# 5v-power.net
KiCad netlist of a schematic drawn in EAGLE
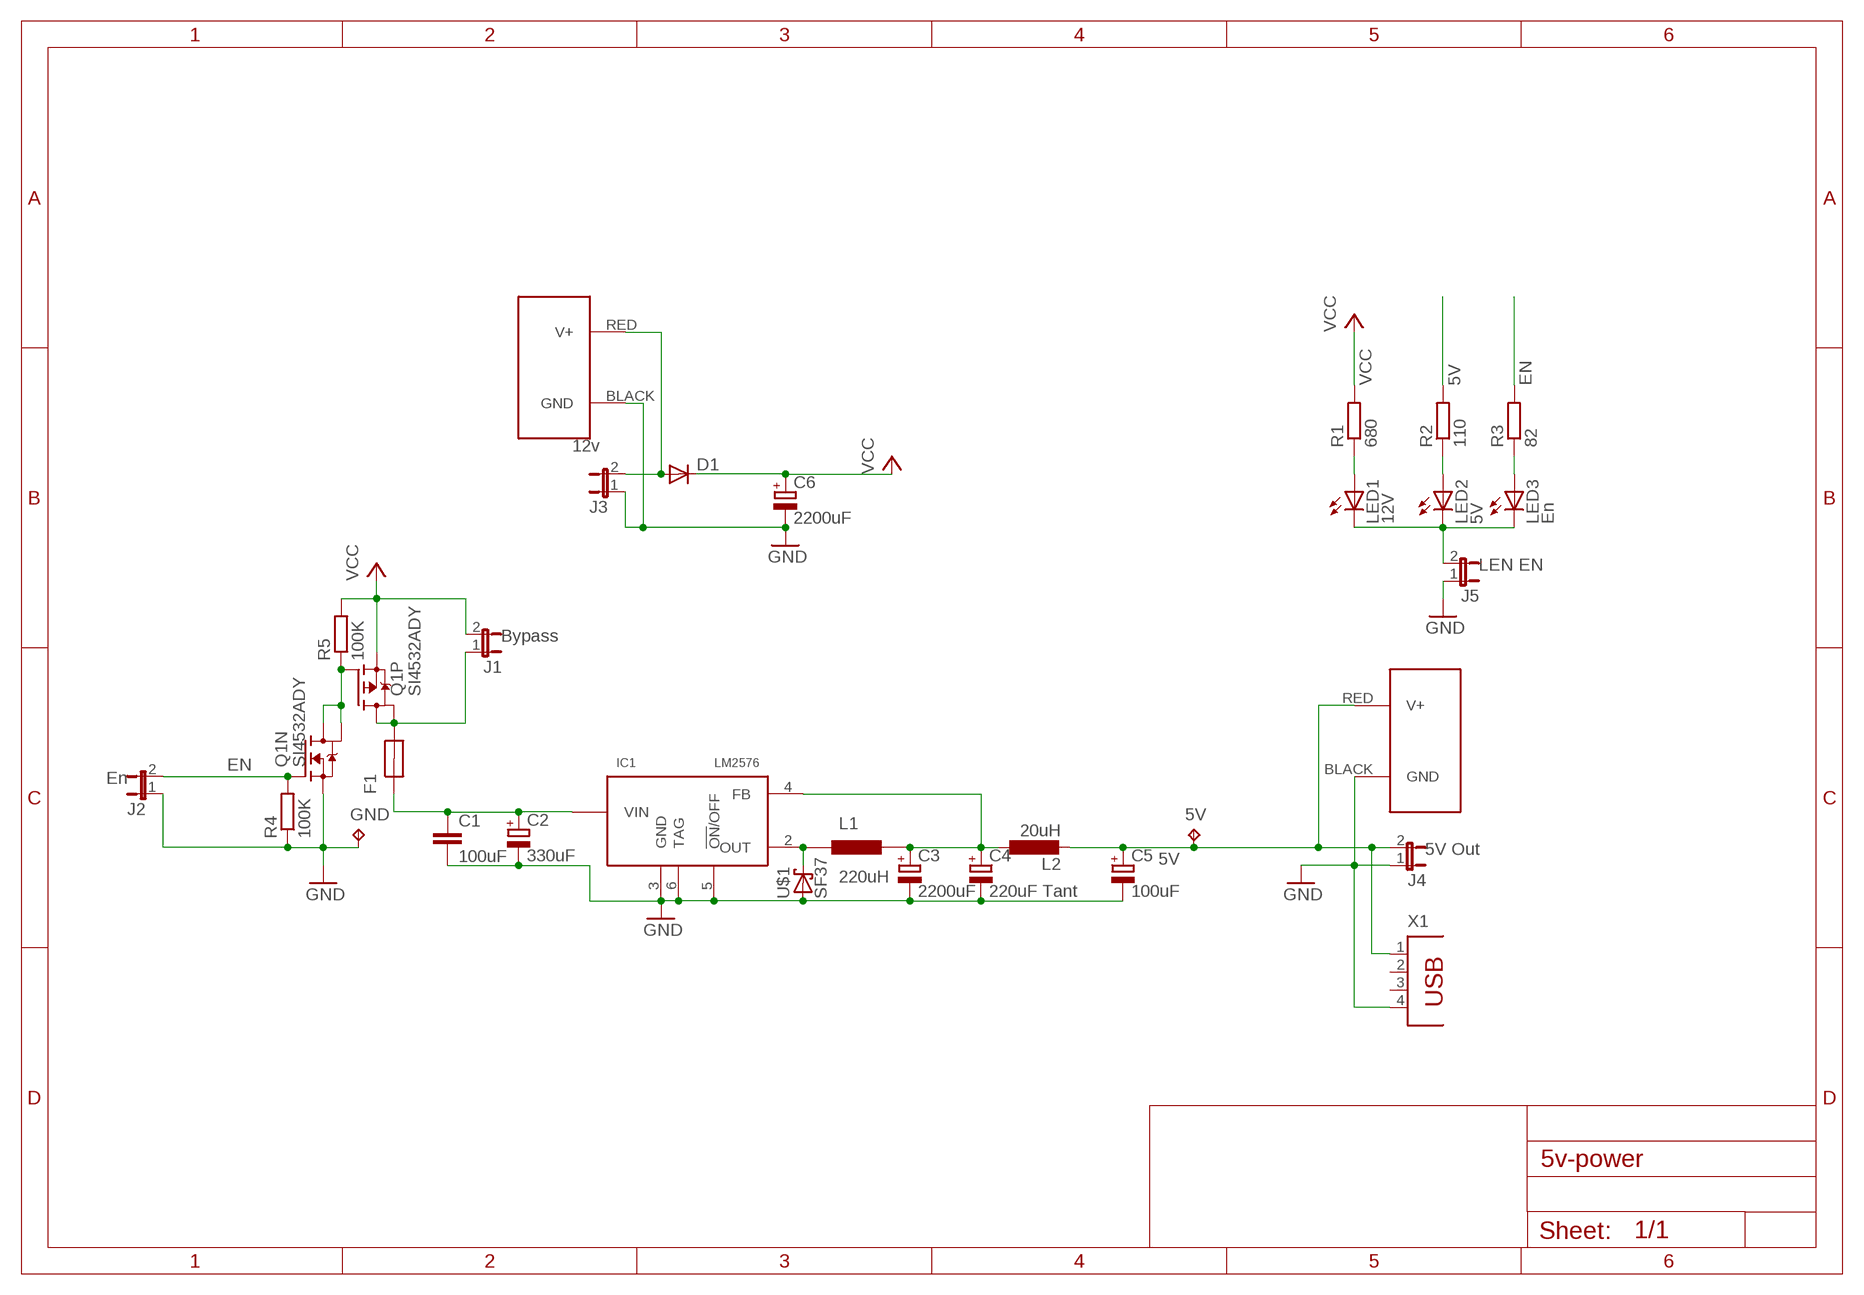
[diagram p0: schematic, sheet 1]

(export (version "E")
  (design (tool "Eeschema 10.0.6"))
  (components
    (comp (ref "5V")
      (value "5V B")
      (footprint "eagle-import:B1,27")
      (libsource (lib "eagle-import") (part "TPB1,27"))
    )
    (comp (ref "C1")
      (value "100uF")
      (footprint "eagle-import:C1210K")
      (libsource (lib "eagle-import") (part "C-EUC1210K"))
    )
    (comp (ref "C2")
      (value "330uF")
      (footprint "eagle-import:E5-8,5")
      (libsource (lib "eagle-import") (part "CPOL-EUE5-8.5"))
    )
    (comp (ref "C3")
      (value "2200uF")
      (footprint "eagle-import:E5-13")
      (libsource (lib "eagle-import") (part "CPOL-EUE5-13"))
    )
    (comp (ref "C4")
      (value "220uF Tant")
      (footprint "eagle-import:B_3528-21R")
      (libsource (lib "eagle-import") (part "CPOL-EUB/3528-21R"))
    )
    (comp (ref "C5")
      (value "100uF")
      (footprint "eagle-import:PANASONIC_E")
      (libsource (lib "eagle-import") (part "CPOL-EUE"))
    )
    (comp (ref "C6")
      (value "2200uF")
      (footprint "eagle-import:E5-13")
      (libsource (lib "eagle-import") (part "CPOL-EUE5-13"))
    )
    (comp (ref "D1")
      (value "DIODE-SMB")
      (footprint "eagle-import:SMB")
      (libsource (lib "eagle-import") (part "DIODE-SMB"))
    )
    (comp (ref "F1")
      (value "MF-MSMF110")
      (footprint "eagle-import:1812")
      (libsource (lib "eagle-import") (part "MF-MSMF110"))
    )
    (comp (ref "GND")
      (value "5V B")
      (footprint "eagle-import:B1,27")
      (libsource (lib "eagle-import") (part "TPB1,27"))
    )
    (comp (ref "IC1")
      (value "LM2576")
      (footprint "eagle-import:TO263")
      (libsource (lib "eagle-import") (part "LM2576"))
    )
    (comp (ref "J1")
      (value "Bypass")
      (footprint "eagle-import:2-MOLEX")
      (libsource (lib "eagle-import") (part "2-PIN-MOLEX"))
    )
    (comp (ref "J2")
      (value "En")
      (footprint "eagle-import:2-MOLEX")
      (libsource (lib "eagle-import") (part "2-PIN-MOLEX"))
    )
    (comp (ref "J3")
      (value "12v")
      (footprint "eagle-import:2-MOLEX")
      (libsource (lib "eagle-import") (part "2-PIN-MOLEX"))
    )
    (comp (ref "J4")
      (value "5V Out")
      (footprint "eagle-import:2-MOLEX")
      (libsource (lib "eagle-import") (part "2-PIN-MOLEX"))
    )
    (comp (ref "J5")
      (value "LEN EN")
      (footprint "eagle-import:2-MOLEX")
      (libsource (lib "eagle-import") (part "2-PIN-MOLEX"))
    )
    (comp (ref "J6")
      (value "POWERPOLE_POWER10AWG")
      (footprint "eagle-import:POWERPOLE_PAIR_10AWG")
      (libsource (lib "eagle-import") (part "POWERPOLE_POWER10AWG"))
    )
    (comp (ref "J7")
      (value "POWERPOLE_POWER10AWG")
      (footprint "eagle-import:POWERPOLE_PAIR_10AWG")
      (libsource (lib "eagle-import") (part "POWERPOLE_POWER10AWG"))
    )
    (comp (ref "L1")
      (value "220uH")
      (footprint "eagle-import:DR127")
      (libsource (lib "eagle-import") (part "DR127-221-R"))
    )
    (comp (ref "L2")
      (value "20uH")
      (footprint "eagle-import:6000-XXXX-RC")
      (libsource (lib "eagle-import") (part "L-EU6000-XXX-RC"))
    )
    (comp (ref "LED1")
      (value "12V")
      (footprint "eagle-import:CHIP-LED0805")
      (libsource (lib "eagle-import") (part "LEDCHIP-LED0805"))
    )
    (comp (ref "LED2")
      (value "5V")
      (footprint "eagle-import:CHIP-LED0805")
      (libsource (lib "eagle-import") (part "LEDCHIP-LED0805"))
    )
    (comp (ref "LED3")
      (value "En")
      (footprint "eagle-import:CHIP-LED0805")
      (libsource (lib "eagle-import") (part "LEDCHIP-LED0805"))
    )
    (comp (ref "Q1")
      (value "SI4532ADY")
      (footprint "eagle-import:SO8")
      (libsource (lib "eagle-import") (part "SI4532ADY"))
    )
    (comp (ref "R1")
      (value "680")
      (footprint "eagle-import:R0805")
      (libsource (lib "eagle-import") (part "R-EU_R0805"))
    )
    (comp (ref "R2")
      (value "110")
      (footprint "eagle-import:R0805")
      (libsource (lib "eagle-import") (part "R-EU_R0805"))
    )
    (comp (ref "R3")
      (value "82")
      (footprint "eagle-import:R0805")
      (libsource (lib "eagle-import") (part "R-EU_R0805"))
    )
    (comp (ref "R4")
      (value "100K")
      (footprint "eagle-import:R0805")
      (libsource (lib "eagle-import") (part "R-EU_R0805"))
    )
    (comp (ref "R5")
      (value "100K")
      (footprint "eagle-import:R0805")
      (libsource (lib "eagle-import") (part "R-EU_R0805"))
    )
    (comp (ref "U$1")
      (value "SF37")
      (footprint "eagle-import:DO-201AD")
      (libsource (lib "eagle-import") (part "SF37"))
    )
    (comp (ref "X1")
      (value "PN87520")
      (footprint "eagle-import:PN87520")
      (libsource (lib "eagle-import") (part "PN87520"))
    )
  )
  (nets
    (net (code "1") (name "/5V") (class "Default")
      (node (ref "5V") (pin "TP") (pinfunction "TP_TP") (pintype "input"))
      (node (ref "C5") (pin "+") (pinfunction "+_+") (pintype "passive"))
      (node (ref "J4") (pin "2") (pinfunction "2_2") (pintype "passive"))
      (node (ref "J6") (pin "RED") (pinfunction "V+_RED") (pintype "power_in"))
      (node (ref "L2") (pin "2") (pinfunction "2_2") (pintype "passive"))
      (node (ref "R2") (pin "2") (pinfunction "2_2") (pintype "passive"))
      (node (ref "X1") (pin "1") (pinfunction "1_1") (pintype "passive"))
    )
    (net (code "2") (name "/EN") (class "Default")
      (node (ref "J2") (pin "2") (pinfunction "2_2") (pintype "passive"))
      (node (ref "Q1") (pin "2") (pinfunction "G_2") (pintype "passive"))
      (node (ref "R3") (pin "2") (pinfunction "2_2") (pintype "passive"))
      (node (ref "R4") (pin "2") (pinfunction "2_2") (pintype "passive"))
    )
    (net (code "3") (name "GND") (class "Default")
      (node (ref "C1") (pin "2") (pinfunction "2_2") (pintype "passive"))
      (node (ref "C2") (pin "-") (pinfunction "-_-") (pintype "passive"))
      (node (ref "C3") (pin "-") (pinfunction "-_-") (pintype "passive"))
      (node (ref "C4") (pin "-") (pinfunction "-_-") (pintype "passive"))
      (node (ref "C5") (pin "-") (pinfunction "-_-") (pintype "passive"))
      (node (ref "C6") (pin "-") (pinfunction "-_-") (pintype "passive"))
      (node (ref "GND") (pin "TP") (pinfunction "TP_TP") (pintype "input"))
      (node (ref "IC1") (pin "3") (pinfunction "GND_3") (pintype "power_in"))
      (node (ref "IC1") (pin "5") (pinfunction "~{ON}/OFF_5") (pintype "input"))
      (node (ref "IC1") (pin "6") (pinfunction "TAG_6") (pintype "power_in"))
      (node (ref "J2") (pin "1") (pinfunction "1_1") (pintype "passive"))
      (node (ref "J3") (pin "1") (pinfunction "1_1") (pintype "passive"))
      (node (ref "J4") (pin "1") (pinfunction "1_1") (pintype "passive"))
      (node (ref "J5") (pin "1") (pinfunction "1_1") (pintype "passive"))
      (node (ref "J6") (pin "BLACK") (pinfunction "GND_BLACK") (pintype "power_in"))
      (node (ref "J7") (pin "BLACK") (pinfunction "GND_BLACK") (pintype "power_in"))
      (node (ref "Q1") (pin "1") (pinfunction "S_1") (pintype "passive"))
      (node (ref "R4") (pin "1") (pinfunction "1_1") (pintype "passive"))
      (node (ref "U$1") (pin "2") (pinfunction "A_2") (pintype "passive"))
      (node (ref "X1") (pin "4") (pinfunction "4_4") (pintype "passive"))
    )
    (net (code "4") (name "Net-(F1-P$1)") (class "Default")
      (node (ref "C1") (pin "1") (pinfunction "1_1") (pintype "passive"))
      (node (ref "C2") (pin "+") (pinfunction "+_+") (pintype "passive"))
      (node (ref "F1") (pin "1") (pinfunction "P$1_1") (pintype "bidirectional"))
      (node (ref "IC1") (pin "1") (pinfunction "VIN_1") (pintype "power_in"))
    )
    (net (code "5") (name "Net-(F1-P$2)") (class "Default")
      (node (ref "F1") (pin "2") (pinfunction "P$2_2") (pintype "bidirectional"))
      (node (ref "J1") (pin "1") (pinfunction "1_1") (pintype "passive"))
      (node (ref "Q1") (pin "5") (pinfunction "D_5") (pintype "passive"))
      (node (ref "Q1") (pin "6") (pinfunction "D_6") (pintype "passive"))
    )
    (net (code "6") (name "Net-(IC1-FB)") (class "Default")
      (node (ref "C3") (pin "+") (pinfunction "+_+") (pintype "passive"))
      (node (ref "C4") (pin "+") (pinfunction "+_+") (pintype "passive"))
      (node (ref "IC1") (pin "4") (pinfunction "FB_4") (pintype "passive"))
      (node (ref "L1") (pin "2") (pinfunction "P$2_2") (pintype "bidirectional"))
      (node (ref "L2") (pin "1") (pinfunction "1_1") (pintype "passive"))
    )
    (net (code "7") (name "Net-(IC1-OUT)") (class "Default")
      (node (ref "IC1") (pin "2") (pinfunction "OUT_2") (pintype "output"))
      (node (ref "L1") (pin "1") (pinfunction "P$1_1") (pintype "bidirectional"))
      (node (ref "U$1") (pin "1") (pinfunction "C_1") (pintype "passive"))
    )
    (net (code "8") (name "Net-(J5-Pad2)") (class "Default")
      (node (ref "J5") (pin "2") (pinfunction "2_2") (pintype "passive"))
      (node (ref "LED1") (pin "C") (pinfunction "C_C") (pintype "passive"))
      (node (ref "LED2") (pin "C") (pinfunction "C_C") (pintype "passive"))
      (node (ref "LED3") (pin "C") (pinfunction "C_C") (pintype "passive"))
    )
    (net (code "9") (name "Net-(J7-V+)") (class "Default")
      (node (ref "D1") (pin "A") (pinfunction "A_A") (pintype "passive"))
      (node (ref "J3") (pin "2") (pinfunction "2_2") (pintype "passive"))
      (node (ref "J7") (pin "RED") (pinfunction "V+_RED") (pintype "power_in"))
    )
    (net (code "10") (name "Net-(LED1-PadA)") (class "Default")
      (node (ref "LED1") (pin "A") (pinfunction "A_A") (pintype "passive"))
      (node (ref "R1") (pin "1") (pinfunction "1_1") (pintype "passive"))
    )
    (net (code "11") (name "Net-(LED2-PadA)") (class "Default")
      (node (ref "LED2") (pin "A") (pinfunction "A_A") (pintype "passive"))
      (node (ref "R2") (pin "1") (pinfunction "1_1") (pintype "passive"))
    )
    (net (code "12") (name "Net-(LED3-PadA)") (class "Default")
      (node (ref "LED3") (pin "A") (pinfunction "A_A") (pintype "passive"))
      (node (ref "R3") (pin "1") (pinfunction "1_1") (pintype "passive"))
    )
    (net (code "13") (name "Net-(Q1B-G)") (class "Default")
      (node (ref "Q1") (pin "4") (pinfunction "G_4") (pintype "passive"))
      (node (ref "Q1") (pin "7") (pinfunction "D_7") (pintype "passive"))
      (node (ref "Q1") (pin "8") (pinfunction "D_8") (pintype "passive"))
      (node (ref "R5") (pin "1") (pinfunction "1_1") (pintype "passive"))
    )
    (net (code "14") (name "VCC") (class "Default")
      (node (ref "C6") (pin "+") (pinfunction "+_+") (pintype "passive"))
      (node (ref "D1") (pin "C") (pinfunction "C_C") (pintype "passive"))
      (node (ref "J1") (pin "2") (pinfunction "2_2") (pintype "passive"))
      (node (ref "Q1") (pin "3") (pinfunction "S_3") (pintype "passive"))
      (node (ref "R1") (pin "2") (pinfunction "2_2") (pintype "passive"))
      (node (ref "R5") (pin "2") (pinfunction "2_2") (pintype "passive"))
    )
    (net (code "15") (name "unconnected-(X1-Pad2)") (class "Default")
      (node (ref "X1") (pin "2") (pinfunction "2_2") (pintype "passive"))
    )
    (net (code "16") (name "unconnected-(X1-Pad3)") (class "Default")
      (node (ref "X1") (pin "3") (pinfunction "3_3") (pintype "passive"))
    )
  )
)
